# SouldBoard.net
KiCad netlist of a schematic drawn in Altium Designer
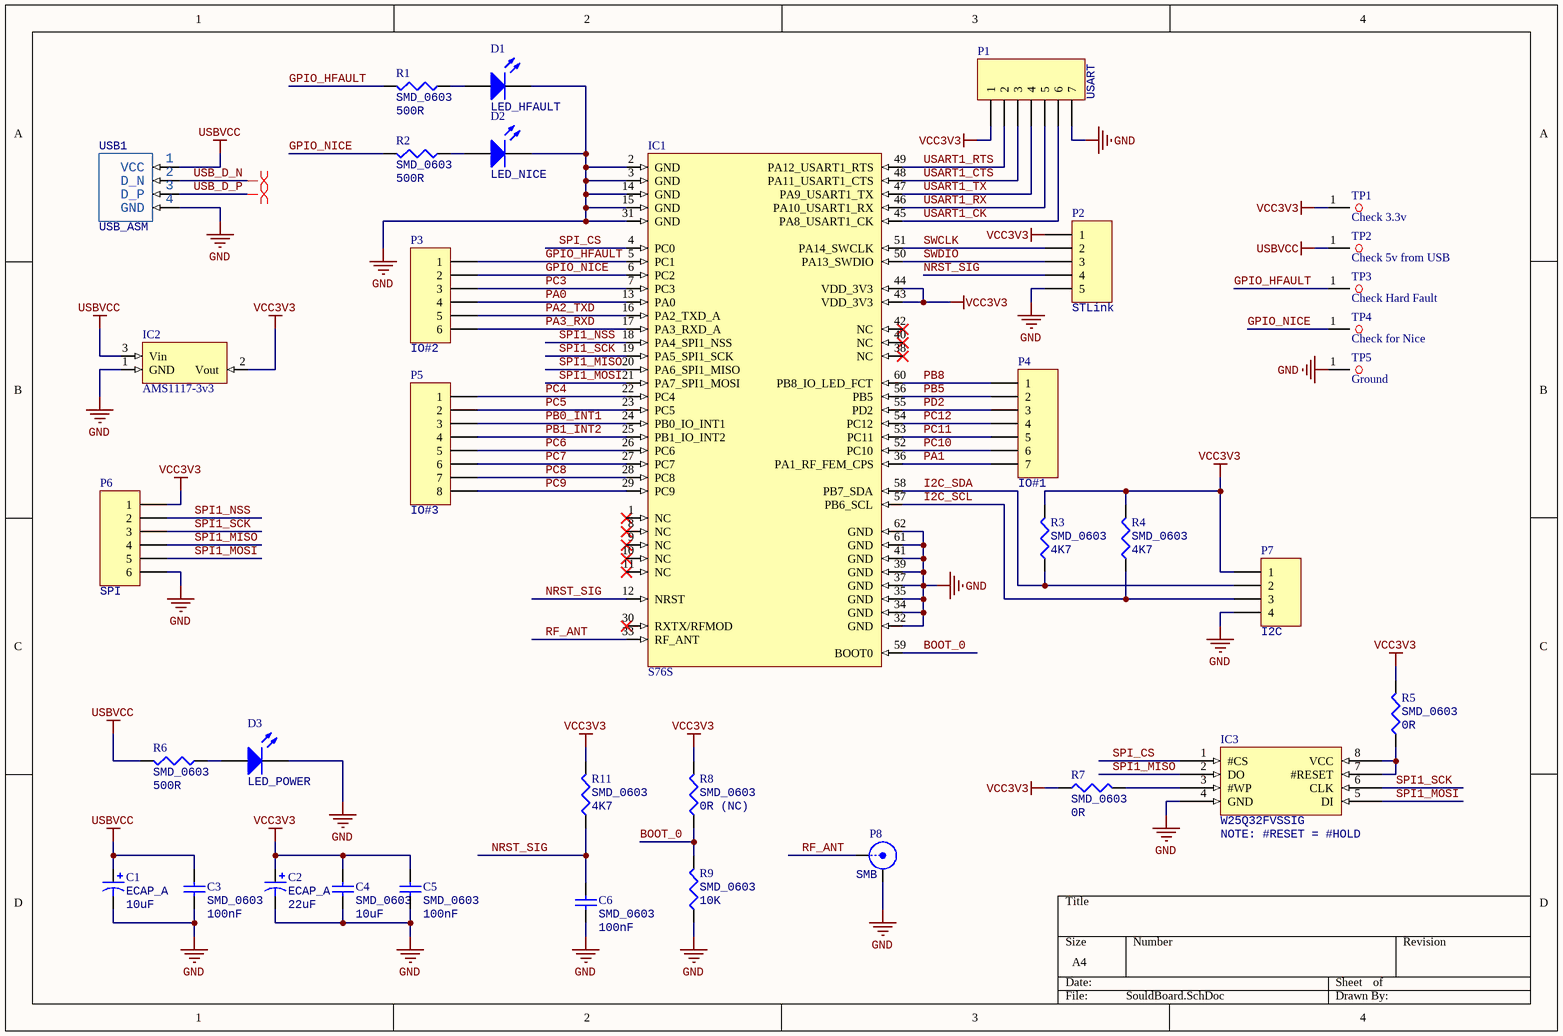
[diagram p0: SouldBoard.SchDoc]

(export (version "E")
  (design (tool "Eeschema 10.0.6"))
  (components
    (comp (ref "C1")
      (value "ECAP_A")
      (footprint "CAPAE4645X63M")
      (description "Polarized Capacitor (Radial)")
      (fields (field (name "ALTIUM_VALUE") "10uF") (field (name "PUBLISHER") "Altium Limited"))
      (libsource (lib "Miscellaneous Devices") (part "Cap Pol1"))
    )
    (comp (ref "C2")
      (value "ECAP_A")
      (footprint "CAPAE4645X63M")
      (description "Polarized Capacitor (Radial)")
      (fields (field (name "ALTIUM_VALUE") "22uF") (field (name "PUBLISHER") "Altium Limited"))
      (libsource (lib "Miscellaneous Devices") (part "Cap Pol1"))
    )
    (comp (ref "C3")
      (value "SMD_0603")
      (footprint "1608[0603]")
      (description "Capacitor (Semiconductor SIM Model)")
      (fields (field (name "ALTIUM_VALUE") "100nF") (field (name "PUBLISHER") "Altium Limited"))
      (libsource (lib "Miscellaneous Devices") (part "Cap Semi"))
    )
    (comp (ref "C4")
      (value "SMD_0603")
      (footprint "1608[0603]")
      (description "Capacitor (Semiconductor SIM Model)")
      (fields (field (name "ALTIUM_VALUE") "10uF") (field (name "PUBLISHER") "Altium Limited"))
      (libsource (lib "Miscellaneous Devices") (part "Cap Semi"))
    )
    (comp (ref "C5")
      (value "SMD_0603")
      (footprint "1608[0603]")
      (description "Capacitor (Semiconductor SIM Model)")
      (fields (field (name "ALTIUM_VALUE") "100nF") (field (name "PUBLISHER") "Altium Limited"))
      (libsource (lib "Miscellaneous Devices") (part "Cap Semi"))
    )
    (comp (ref "C6")
      (value "SMD_0603")
      (footprint "1608[0603]")
      (description "Capacitor (Semiconductor SIM Model)")
      (fields (field (name "ALTIUM_VALUE") "100nF") (field (name "PUBLISHER") "Altium Limited"))
      (libsource (lib "Miscellaneous Devices") (part "Cap Semi"))
    )
    (comp (ref "D1")
      (value "LED_HFAULT")
      (footprint "3.5X2.8X1.9")
      (description "Typical BLUE SiC LED")
      (fields (field (name "PUBLISHER") "Altium Limited"))
      (libsource (lib "Miscellaneous Devices") (part "LED3"))
    )
    (comp (ref "D2")
      (value "LED_NICE")
      (footprint "3.5X2.8X1.9")
      (description "Typical BLUE SiC LED")
      (fields (field (name "PUBLISHER") "Altium Limited"))
      (libsource (lib "Miscellaneous Devices") (part "LED3"))
    )
    (comp (ref "D3")
      (value "LED_POWER")
      (footprint "3.5X2.8X1.9")
      (description "Typical BLUE SiC LED")
      (fields (field (name "PUBLISHER") "Altium Limited"))
      (libsource (lib "Miscellaneous Devices") (part "LED3"))
    )
    (comp (ref "IC1")
      (value "S76S")
      (footprint "S76S")
      (description "LoRa S76S")
      (libsource (lib "DirtyLib") (part "S76S"))
    )
    (comp (ref "IC2")
      (value "AMS1117-3v3")
      (footprint "SOT223")
      (description "AMS1117 5v to 3.3v")
      (libsource (lib "DirtyLib") (part "AMS1117_3V3"))
    )
    (comp (ref "IC3")
      (value "W25Q32FVSSIG")
      (footprint "SOIC8_208mil")
      (description "SPI Flash 32Mbit (4MB)")
      (libsource (lib "Components") (part "W25Q32FVSSIG"))
    )
    (comp (ref "P1")
      (value "USART")
      (footprint "HDR1X7")
      (description "Header, 7-Pin")
      (fields (field (name "PUBLISHER") "Altium Limited"))
      (libsource (lib "Miscellaneous Connectors") (part "Header 7"))
    )
    (comp (ref "P2")
      (value "STLink")
      (footprint "HDR1X5")
      (description "Header, 5-Pin")
      (fields (field (name "PUBLISHER") "Altium Limited"))
      (libsource (lib "Miscellaneous Connectors") (part "Header 5"))
    )
    (comp (ref "P3")
      (value "IO#2")
      (footprint "HDR1X6")
      (description "Header, 6-Pin")
      (fields (field (name "PUBLISHER") "Altium Limited"))
      (libsource (lib "Miscellaneous Connectors") (part "Header 6"))
    )
    (comp (ref "P4")
      (value "IO#1")
      (footprint "HDR1X7")
      (description "Header, 7-Pin")
      (fields (field (name "PUBLISHER") "Altium Limited"))
      (libsource (lib "") (part "Header 7_1"))
    )
    (comp (ref "P5")
      (value "IO#3")
      (footprint "HDR1X8")
      (description "Header, 8-Pin")
      (fields (field (name "PUBLISHER") "Altium Limited"))
      (libsource (lib "Miscellaneous Connectors") (part "Header 8"))
    )
    (comp (ref "P6")
      (value "SPI")
      (footprint "HDR1X6")
      (description "Header, 6-Pin")
      (fields (field (name "PUBLISHER") "Altium Limited"))
      (libsource (lib "Miscellaneous Connectors") (part "Header 6"))
    )
    (comp (ref "P7")
      (value "I2C")
      (footprint "HDR1X4")
      (description "Header, 4-Pin")
      (fields (field (name "PUBLISHER") "Altium Limited"))
      (libsource (lib "Miscellaneous Connectors") (part "Header 4"))
    )
    (comp (ref "P8")
      (value "SMB")
      (footprint "SMB_V-RJ45")
      (description "SMB Straight Connector")
      (fields (field (name "PUBLISHER") "Altium Limited"))
      (libsource (lib "Miscellaneous Connectors") (part "SMB"))
    )
    (comp (ref "R1")
      (value "SMD_0603")
      (footprint "J1-0603")
      (description "Resistor")
      (fields (field (name "ALTIUM_VALUE") "500R") (field (name "PUBLISHER") "Altium Limited"))
      (libsource (lib "Miscellaneous Devices") (part "Res3"))
    )
    (comp (ref "R2")
      (value "SMD_0603")
      (footprint "J1-0603")
      (description "Resistor")
      (fields (field (name "ALTIUM_VALUE") "500R") (field (name "PUBLISHER") "Altium Limited"))
      (libsource (lib "Miscellaneous Devices") (part "Res3"))
    )
    (comp (ref "R3")
      (value "SMD_0603")
      (footprint "J1-0603")
      (description "Resistor")
      (fields (field (name "ALTIUM_VALUE") "4K7") (field (name "PUBLISHER") "Altium Limited"))
      (libsource (lib "Miscellaneous Devices") (part "Res3"))
    )
    (comp (ref "R4")
      (value "SMD_0603")
      (footprint "J1-0603")
      (description "Resistor")
      (fields (field (name "ALTIUM_VALUE") "4K7") (field (name "PUBLISHER") "Altium Limited"))
      (libsource (lib "Miscellaneous Devices") (part "Res3"))
    )
    (comp (ref "R5")
      (value "SMD_0603")
      (footprint "J1-0603")
      (description "Resistor")
      (fields (field (name "ALTIUM_VALUE") "0R") (field (name "PUBLISHER") "Altium Limited"))
      (libsource (lib "Miscellaneous Devices") (part "Res3"))
    )
    (comp (ref "R6")
      (value "SMD_0603")
      (footprint "J1-0603")
      (description "Resistor")
      (fields (field (name "ALTIUM_VALUE") "500R") (field (name "PUBLISHER") "Altium Limited"))
      (libsource (lib "Miscellaneous Devices") (part "Res3"))
    )
    (comp (ref "R7")
      (value "SMD_0603")
      (footprint "J1-0603")
      (description "Resistor")
      (fields (field (name "ALTIUM_VALUE") "0R") (field (name "PUBLISHER") "Altium Limited"))
      (libsource (lib "Miscellaneous Devices") (part "Res3"))
    )
    (comp (ref "R8")
      (value "SMD_0603")
      (footprint "J1-0603")
      (description "Resistor")
      (fields (field (name "ALTIUM_VALUE") "0R (NC)") (field (name "PUBLISHER") "Altium Limited"))
      (libsource (lib "Miscellaneous Devices") (part "Res3"))
    )
    (comp (ref "R9")
      (value "SMD_0603")
      (footprint "J1-0603")
      (description "Resistor")
      (fields (field (name "ALTIUM_VALUE") "10K") (field (name "PUBLISHER") "Altium Limited"))
      (libsource (lib "Miscellaneous Devices") (part "Res3"))
    )
    (comp (ref "R11")
      (value "SMD_0603")
      (footprint "J1-0603")
      (description "Resistor")
      (fields (field (name "ALTIUM_VALUE") "4K7") (field (name "PUBLISHER") "Altium Limited"))
      (libsource (lib "Miscellaneous Devices") (part "Res3"))
    )
    (comp (ref "TP1")
      (value "Check 3.3v")
      (footprint "TestPoint")
      (description "Test Point")
      (libsource (lib "DirtyLib") (part "TP"))
    )
    (comp (ref "TP2")
      (value "Check 5v from USB")
      (footprint "TestPoint")
      (description "Test Point")
      (libsource (lib "DirtyLib") (part "TP"))
    )
    (comp (ref "TP3")
      (value "Check Hard Fault")
      (footprint "TestPoint")
      (description "Test Point")
      (libsource (lib "DirtyLib") (part "TP"))
    )
    (comp (ref "TP4")
      (value "Check for Nice")
      (footprint "TestPoint")
      (description "Test Point")
      (libsource (lib "DirtyLib") (part "TP"))
    )
    (comp (ref "TP5")
      (value "Ground")
      (footprint "TestPoint")
      (description "Test Point")
      (libsource (lib "DirtyLib") (part "TP"))
    )
    (comp (ref "USB1")
      (value "USB_ASM")
      (footprint "PCBComponent_1")
      (description "USB port type ASM")
      (libsource (lib "Components") (part "USB_ASM"))
    )
  )
  (nets
    (net (code "1") (name "/BOOT_0") (class "Default")
      (node (ref "IC1") (pin "59") (pinfunction "BOOT0_59") (pintype "input"))
      (node (ref "R8") (pin "1") (pinfunction "1_1") (pintype "passive"))
      (node (ref "R9") (pin "2") (pinfunction "2_2") (pintype "passive"))
    )
    (net (code "2") (name "/GPIO_HFAULT") (class "Default")
      (node (ref "IC1") (pin "5") (pinfunction "PC1_5") (pintype "input"))
      (node (ref "P3") (pin "1") (pinfunction "1_1") (pintype "passive"))
      (node (ref "R1") (pin "2") (pinfunction "2_2") (pintype "passive"))
      (node (ref "TP3") (pin "1") (pintype "passive"))
    )
    (net (code "3") (name "/GPIO_NICE") (class "Default")
      (node (ref "IC1") (pin "6") (pinfunction "PC2_6") (pintype "input"))
      (node (ref "P3") (pin "2") (pinfunction "2_2") (pintype "passive"))
      (node (ref "R2") (pin "2") (pinfunction "2_2") (pintype "passive"))
      (node (ref "TP4") (pin "1") (pintype "passive"))
    )
    (net (code "4") (name "/I2C_SCL") (class "Default")
      (node (ref "IC1") (pin "57") (pinfunction "PB6_SCL_57") (pintype "input"))
      (node (ref "P7") (pin "3") (pinfunction "3_3") (pintype "passive"))
      (node (ref "R4") (pin "1") (pinfunction "1_1") (pintype "passive"))
    )
    (net (code "5") (name "/I2C_SDA") (class "Default")
      (node (ref "IC1") (pin "58") (pinfunction "PB7_SDA_58") (pintype "input"))
      (node (ref "P7") (pin "2") (pinfunction "2_2") (pintype "passive"))
      (node (ref "R3") (pin "1") (pinfunction "1_1") (pintype "passive"))
    )
    (net (code "6") (name "/NRST_SIG") (class "Default")
      (node (ref "C6") (pin "2") (pinfunction "2_2") (pintype "passive"))
      (node (ref "IC1") (pin "12") (pinfunction "NRST_12") (pintype "input"))
      (node (ref "P2") (pin "4") (pinfunction "4_4") (pintype "passive"))
      (node (ref "R11") (pin "1") (pinfunction "1_1") (pintype "passive"))
    )
    (net (code "7") (name "/PA0") (class "Default")
      (node (ref "IC1") (pin "13") (pinfunction "PA0_13") (pintype "input"))
      (node (ref "P3") (pin "4") (pinfunction "4_4") (pintype "passive"))
    )
    (net (code "8") (name "/PA1") (class "Default")
      (node (ref "IC1") (pin "36") (pinfunction "PA1_RF_FEM_CPS_36") (pintype "input"))
      (node (ref "P4") (pin "7") (pinfunction "7_7") (pintype "passive"))
    )
    (net (code "9") (name "/PA2_TXD") (class "Default")
      (node (ref "IC1") (pin "16") (pinfunction "PA2_TXD_A_16") (pintype "input"))
      (node (ref "P3") (pin "5") (pinfunction "5_5") (pintype "passive"))
    )
    (net (code "10") (name "/PA3_RXD") (class "Default")
      (node (ref "IC1") (pin "17") (pinfunction "PA3_RXD_A_17") (pintype "input"))
      (node (ref "P3") (pin "6") (pinfunction "6_6") (pintype "passive"))
    )
    (net (code "11") (name "/PB0_INT1") (class "Default")
      (node (ref "IC1") (pin "24") (pinfunction "PB0_IO_INT1_24") (pintype "input"))
      (node (ref "P5") (pin "3") (pinfunction "3_3") (pintype "passive"))
    )
    (net (code "12") (name "/PB1_INT2") (class "Default")
      (node (ref "IC1") (pin "25") (pinfunction "PB1_IO_INT2_25") (pintype "input"))
      (node (ref "P5") (pin "4") (pinfunction "4_4") (pintype "passive"))
    )
    (net (code "13") (name "/PB5") (class "Default")
      (node (ref "IC1") (pin "56") (pinfunction "PB5_56") (pintype "input"))
      (node (ref "P4") (pin "2") (pinfunction "2_2") (pintype "passive"))
    )
    (net (code "14") (name "/PB8") (class "Default")
      (node (ref "IC1") (pin "60") (pinfunction "PB8_IO_LED_FCT_60") (pintype "input"))
      (node (ref "P4") (pin "1") (pinfunction "1_1") (pintype "passive"))
    )
    (net (code "15") (name "/PC3") (class "Default")
      (node (ref "IC1") (pin "7") (pinfunction "PC3_7") (pintype "input"))
      (node (ref "P3") (pin "3") (pinfunction "3_3") (pintype "passive"))
    )
    (net (code "16") (name "/PC4") (class "Default")
      (node (ref "IC1") (pin "22") (pinfunction "PC4_22") (pintype "input"))
      (node (ref "P5") (pin "1") (pinfunction "1_1") (pintype "passive"))
    )
    (net (code "17") (name "/PC5") (class "Default")
      (node (ref "IC1") (pin "23") (pinfunction "PC5_23") (pintype "input"))
      (node (ref "P5") (pin "2") (pinfunction "2_2") (pintype "passive"))
    )
    (net (code "18") (name "/PC6") (class "Default")
      (node (ref "IC1") (pin "26") (pinfunction "PC6_26") (pintype "input"))
      (node (ref "P5") (pin "5") (pinfunction "5_5") (pintype "passive"))
    )
    (net (code "19") (name "/PC7") (class "Default")
      (node (ref "IC1") (pin "27") (pinfunction "PC7_27") (pintype "input"))
      (node (ref "P5") (pin "6") (pinfunction "6_6") (pintype "passive"))
    )
    (net (code "20") (name "/PC8") (class "Default")
      (node (ref "IC1") (pin "28") (pinfunction "PC8_28") (pintype "input"))
      (node (ref "P5") (pin "7") (pinfunction "7_7") (pintype "passive"))
    )
    (net (code "21") (name "/PC9") (class "Default")
      (node (ref "IC1") (pin "29") (pinfunction "PC9_29") (pintype "input"))
      (node (ref "P5") (pin "8") (pinfunction "8_8") (pintype "passive"))
    )
    (net (code "22") (name "/PC10") (class "Default")
      (node (ref "IC1") (pin "52") (pinfunction "PC10_52") (pintype "input"))
      (node (ref "P4") (pin "6") (pinfunction "6_6") (pintype "passive"))
    )
    (net (code "23") (name "/PC11") (class "Default")
      (node (ref "IC1") (pin "53") (pinfunction "PC11_53") (pintype "input"))
      (node (ref "P4") (pin "5") (pinfunction "5_5") (pintype "passive"))
    )
    (net (code "24") (name "/PC12") (class "Default")
      (node (ref "IC1") (pin "54") (pinfunction "PC12_54") (pintype "input"))
      (node (ref "P4") (pin "4") (pinfunction "4_4") (pintype "passive"))
    )
    (net (code "25") (name "/PD2") (class "Default")
      (node (ref "IC1") (pin "55") (pinfunction "PD2_55") (pintype "input"))
      (node (ref "P4") (pin "3") (pinfunction "3_3") (pintype "passive"))
    )
    (net (code "26") (name "/RF_ANT") (class "Default")
      (node (ref "IC1") (pin "33") (pinfunction "RF_ANT_33") (pintype "input"))
      (node (ref "P8") (pin "1") (pinfunction "X_1") (pintype "passive"))
    )
    (net (code "27") (name "/SPI1_MISO") (class "Default")
      (node (ref "IC1") (pin "20") (pinfunction "PA6_SPI1_MISO_20") (pintype "input"))
      (node (ref "IC3") (pin "2") (pinfunction "DO_2") (pintype "input"))
      (node (ref "P6") (pin "4") (pinfunction "4_4") (pintype "passive"))
    )
    (net (code "28") (name "/SPI1_MOSI") (class "Default")
      (node (ref "IC1") (pin "21") (pinfunction "PA7_SPI1_MOSI_21") (pintype "input"))
      (node (ref "IC3") (pin "5") (pinfunction "DI_5") (pintype "input"))
      (node (ref "P6") (pin "5") (pinfunction "5_5") (pintype "passive"))
    )
    (net (code "29") (name "/SPI1_NSS") (class "Default")
      (node (ref "IC1") (pin "18") (pinfunction "PA4_SPI1_NSS_18") (pintype "input"))
      (node (ref "P6") (pin "2") (pinfunction "2_2") (pintype "passive"))
    )
    (net (code "30") (name "/SPI1_SCK") (class "Default")
      (node (ref "IC1") (pin "19") (pinfunction "PA5_SPI1_SCK_19") (pintype "input"))
      (node (ref "IC3") (pin "6") (pinfunction "CLK_6") (pintype "input"))
      (node (ref "P6") (pin "3") (pinfunction "3_3") (pintype "passive"))
    )
    (net (code "31") (name "/SPI_CS") (class "Default")
      (node (ref "IC1") (pin "4") (pinfunction "PC0_4") (pintype "input"))
      (node (ref "IC3") (pin "1") (pinfunction "#CS_1") (pintype "input"))
    )
    (net (code "32") (name "/SWCLK") (class "Default")
      (node (ref "IC1") (pin "51") (pinfunction "PA14_SWCLK_51") (pintype "input"))
      (node (ref "P2") (pin "2") (pinfunction "2_2") (pintype "passive"))
    )
    (net (code "33") (name "/SWDIO") (class "Default")
      (node (ref "IC1") (pin "50") (pinfunction "PA13_SWDIO_50") (pintype "input"))
      (node (ref "P2") (pin "3") (pinfunction "3_3") (pintype "passive"))
    )
    (net (code "34") (name "/USART1_CK") (class "Default")
      (node (ref "IC1") (pin "45") (pinfunction "PA8_USART1_CK_45") (pintype "input"))
      (node (ref "P1") (pin "6") (pinfunction "6_6") (pintype "passive"))
    )
    (net (code "35") (name "/USART1_CTS") (class "Default")
      (node (ref "IC1") (pin "48") (pinfunction "PA11_USART1_CTS_48") (pintype "input"))
      (node (ref "P1") (pin "3") (pinfunction "3_3") (pintype "passive"))
    )
    (net (code "36") (name "/USART1_RTS") (class "Default")
      (node (ref "IC1") (pin "49") (pinfunction "PA12_USART1_RTS_49") (pintype "input"))
      (node (ref "P1") (pin "2") (pinfunction "2_2") (pintype "passive"))
    )
    (net (code "37") (name "/USART1_RX") (class "Default")
      (node (ref "IC1") (pin "46") (pinfunction "PA10_USART1_RX_46") (pintype "input"))
      (node (ref "P1") (pin "5") (pinfunction "5_5") (pintype "passive"))
    )
    (net (code "38") (name "/USART1_TX") (class "Default")
      (node (ref "IC1") (pin "47") (pinfunction "PA9_USART1_TX_47") (pintype "input"))
      (node (ref "P1") (pin "4") (pinfunction "4_4") (pintype "passive"))
    )
    (net (code "39") (name "/USB_D_N") (class "Default")
      (node (ref "USB1") (pin "2") (pinfunction "D_N_2") (pintype "input"))
    )
    (net (code "40") (name "/USB_D_P") (class "Default")
      (node (ref "USB1") (pin "3") (pinfunction "D_P_3") (pintype "input"))
    )
    (net (code "41") (name "GND") (class "Default")
      (node (ref "C1") (pin "2") (pinfunction "2_2") (pintype "passive"))
      (node (ref "C2") (pin "2") (pinfunction "2_2") (pintype "passive"))
      (node (ref "C3") (pin "1") (pinfunction "1_1") (pintype "passive"))
      (node (ref "C4") (pin "1") (pinfunction "1_1") (pintype "passive"))
      (node (ref "C5") (pin "1") (pinfunction "1_1") (pintype "passive"))
      (node (ref "C6") (pin "1") (pinfunction "1_1") (pintype "passive"))
      (node (ref "D1") (pin "2") (pinfunction "K_2") (pintype "passive"))
      (node (ref "D2") (pin "2") (pinfunction "K_2") (pintype "passive"))
      (node (ref "D3") (pin "2") (pinfunction "K_2") (pintype "passive"))
      (node (ref "IC1") (pin "14") (pinfunction "GND_14") (pintype "input"))
      (node (ref "IC1") (pin "15") (pinfunction "GND_15") (pintype "input"))
      (node (ref "IC1") (pin "2") (pinfunction "GND_2") (pintype "input"))
      (node (ref "IC1") (pin "3") (pinfunction "GND_3") (pintype "input"))
      (node (ref "IC1") (pin "31") (pinfunction "GND_31") (pintype "input"))
      (node (ref "IC1") (pin "32") (pinfunction "GND_32") (pintype "input"))
      (node (ref "IC1") (pin "34") (pinfunction "GND_34") (pintype "input"))
      (node (ref "IC1") (pin "35") (pinfunction "GND_35") (pintype "input"))
      (node (ref "IC1") (pin "37") (pinfunction "GND_37") (pintype "input"))
      (node (ref "IC1") (pin "39") (pinfunction "GND_39") (pintype "input"))
      (node (ref "IC1") (pin "41") (pinfunction "GND_41") (pintype "input"))
      (node (ref "IC1") (pin "61") (pinfunction "GND_61") (pintype "input"))
      (node (ref "IC1") (pin "62") (pinfunction "GND_62") (pintype "input"))
      (node (ref "IC2") (pin "1") (pinfunction "GND_1") (pintype "input"))
      (node (ref "IC3") (pin "4") (pinfunction "GND_4") (pintype "input"))
      (node (ref "P1") (pin "7") (pinfunction "7_7") (pintype "passive"))
      (node (ref "P2") (pin "5") (pinfunction "5_5") (pintype "passive"))
      (node (ref "P6") (pin "6") (pinfunction "6_6") (pintype "passive"))
      (node (ref "P7") (pin "4") (pinfunction "4_4") (pintype "passive"))
      (node (ref "P8") (pin "2") (pinfunction "Y_2") (pintype "passive"))
      (node (ref "R9") (pin "1") (pinfunction "1_1") (pintype "passive"))
      (node (ref "TP5") (pin "1") (pintype "passive"))
      (node (ref "USB1") (pin "4") (pinfunction "GND_4") (pintype "input"))
    )
    (net (code "42") (name "Net-(D1-A)") (class "Default")
      (node (ref "D1") (pin "1") (pinfunction "A_1") (pintype "passive"))
      (node (ref "R1") (pin "1") (pinfunction "1_1") (pintype "passive"))
    )
    (net (code "43") (name "Net-(D2-A)") (class "Default")
      (node (ref "D2") (pin "1") (pinfunction "A_1") (pintype "passive"))
      (node (ref "R2") (pin "1") (pinfunction "1_1") (pintype "passive"))
    )
    (net (code "44") (name "Net-(D3-A)") (class "Default")
      (node (ref "D3") (pin "1") (pinfunction "A_1") (pintype "passive"))
      (node (ref "R6") (pin "1") (pinfunction "1_1") (pintype "passive"))
    )
    (net (code "45") (name "Net-(IC3-#RESET)") (class "Default")
      (node (ref "IC3") (pin "7") (pinfunction "#RESET_7") (pintype "input"))
      (node (ref "IC3") (pin "8") (pinfunction "VCC_8") (pintype "input"))
      (node (ref "R5") (pin "1") (pinfunction "1_1") (pintype "passive"))
    )
    (net (code "46") (name "Net-(IC3-#WP)") (class "Default")
      (node (ref "IC3") (pin "3") (pinfunction "#WP_3") (pintype "input"))
      (node (ref "R7") (pin "2") (pinfunction "2_2") (pintype "passive"))
    )
    (net (code "47") (name "USBVCC") (class "Default")
      (node (ref "C1") (pin "1") (pinfunction "1_1") (pintype "passive"))
      (node (ref "C3") (pin "2") (pinfunction "2_2") (pintype "passive"))
      (node (ref "IC2") (pin "3") (pinfunction "Vin_3") (pintype "input"))
      (node (ref "R6") (pin "2") (pinfunction "2_2") (pintype "passive"))
      (node (ref "TP2") (pin "1") (pintype "passive"))
      (node (ref "USB1") (pin "1") (pinfunction "VCC_1") (pintype "input"))
    )
    (net (code "48") (name "VCC3V3") (class "Default")
      (node (ref "C2") (pin "1") (pinfunction "1_1") (pintype "passive"))
      (node (ref "C4") (pin "2") (pinfunction "2_2") (pintype "passive"))
      (node (ref "C5") (pin "2") (pinfunction "2_2") (pintype "passive"))
      (node (ref "IC1") (pin "43") (pinfunction "VDD_3V3_43") (pintype "input"))
      (node (ref "IC1") (pin "44") (pinfunction "VDD_3V3_44") (pintype "input"))
      (node (ref "IC2") (pin "2") (pinfunction "Vout_2") (pintype "input"))
      (node (ref "P1") (pin "1") (pinfunction "1_1") (pintype "passive"))
      (node (ref "P2") (pin "1") (pinfunction "1_1") (pintype "passive"))
      (node (ref "P6") (pin "1") (pinfunction "1_1") (pintype "passive"))
      (node (ref "P7") (pin "1") (pinfunction "1_1") (pintype "passive"))
      (node (ref "R11") (pin "2") (pinfunction "2_2") (pintype "passive"))
      (node (ref "R3") (pin "2") (pinfunction "2_2") (pintype "passive"))
      (node (ref "R4") (pin "2") (pinfunction "2_2") (pintype "passive"))
      (node (ref "R5") (pin "2") (pinfunction "2_2") (pintype "passive"))
      (node (ref "R7") (pin "1") (pinfunction "1_1") (pintype "passive"))
      (node (ref "R8") (pin "2") (pinfunction "2_2") (pintype "passive"))
      (node (ref "TP1") (pin "1") (pintype "passive"))
    )
    (net (code "49") (name "unconnected-(IC1-NC-Pad1)") (class "Default")
      (node (ref "IC1") (pin "1") (pinfunction "NC_1") (pintype "input+no_connect"))
    )
    (net (code "50") (name "unconnected-(IC1-NC-Pad8)") (class "Default")
      (node (ref "IC1") (pin "8") (pinfunction "NC_8") (pintype "input+no_connect"))
    )
    (net (code "51") (name "unconnected-(IC1-NC-Pad9)") (class "Default")
      (node (ref "IC1") (pin "9") (pinfunction "NC_9") (pintype "input+no_connect"))
    )
    (net (code "52") (name "unconnected-(IC1-NC-Pad10)") (class "Default")
      (node (ref "IC1") (pin "10") (pinfunction "NC_10") (pintype "input+no_connect"))
    )
    (net (code "53") (name "unconnected-(IC1-NC-Pad11)") (class "Default")
      (node (ref "IC1") (pin "11") (pinfunction "NC_11") (pintype "input+no_connect"))
    )
    (net (code "54") (name "unconnected-(IC1-NC-Pad38)") (class "Default")
      (node (ref "IC1") (pin "38") (pinfunction "NC_38") (pintype "input+no_connect"))
    )
    (net (code "55") (name "unconnected-(IC1-NC-Pad40)") (class "Default")
      (node (ref "IC1") (pin "40") (pinfunction "NC_40") (pintype "input+no_connect"))
    )
    (net (code "56") (name "unconnected-(IC1-NC-Pad42)") (class "Default")
      (node (ref "IC1") (pin "42") (pinfunction "NC_42") (pintype "input+no_connect"))
    )
    (net (code "57") (name "unconnected-(IC1-RXTX{slash}RFMOD-Pad30)") (class "Default")
      (node (ref "IC1") (pin "30") (pinfunction "RXTX/RFMOD_30") (pintype "input+no_connect"))
    )
  )
)
